# STATION.net
KiCad netlist of a schematic drawn in Altium Designer
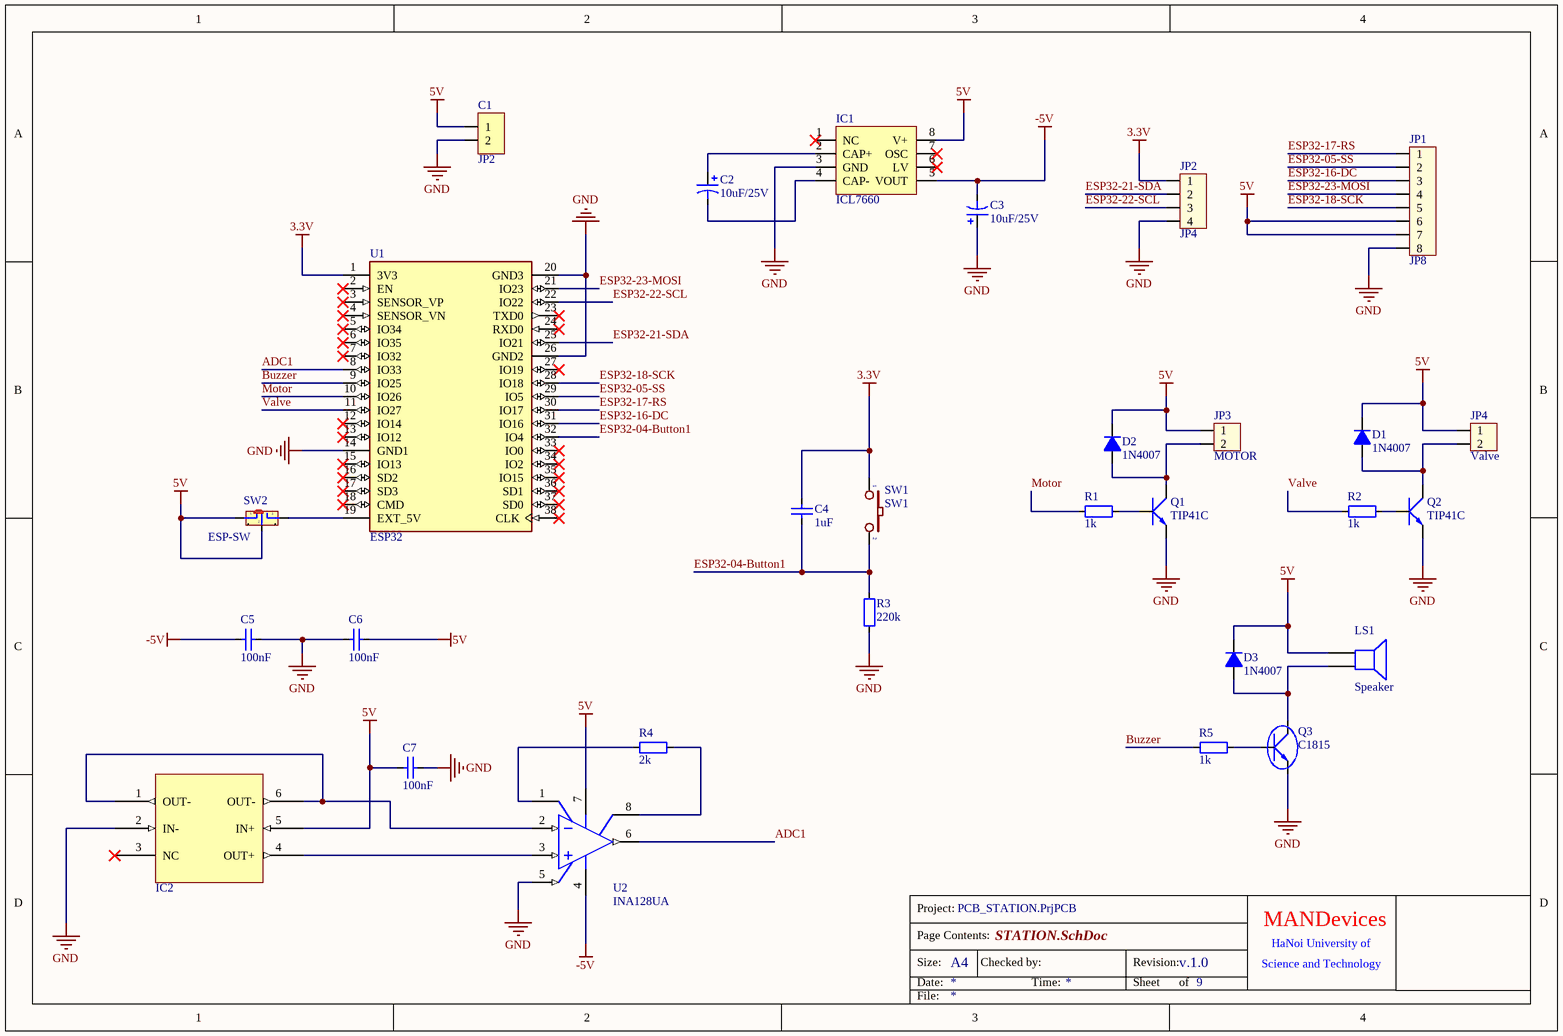
[diagram p0: STATION.SchDoc]

(export (version "E")
  (design (tool "Eeschema 10.0.6"))
  (components
    (comp (ref "C1")
      (value "JP2")
      (footprint "JP2-C1T")
      (description "WR-PHD 2.54 mm Angled Socket Header")
      (fields
        (field (name "MANUFACTURER") "Würth Elektronik eiSos GmbH")
        (field (name "PARTNO") "613002143121")
        (field (name "CREATED BY") "Karrer Zheng")
      )
      (libsource (lib "My Library") (part "JP2"))
    )
    (comp (ref "C2")
      (value "10uF/25V")
      (footprint "C8mm")
      (description "Polarized Capacitor (Axial)")
      (fields (field (name "PUBLISHER") "Altium Limited"))
      (libsource (lib "My Library") (part "Cap Pol"))
    )
    (comp (ref "C3")
      (value "10uF/25V")
      (footprint "C8mm")
      (description "Polarized Capacitor (Axial)")
      (fields (field (name "PUBLISHER") "Altium Limited"))
      (libsource (lib "My Library") (part "Cap Pol"))
    )
    (comp (ref "C4")
      (value "1uF")
      (footprint "CAP_0805")
      (description "Capacitor")
      (fields (field (name "PUBLISHER") "Altium Limited"))
      (libsource (lib "My Library") (part "CapSMD"))
    )
    (comp (ref "C5")
      (value "100nF")
      (footprint "CAP_0805")
      (description "Capacitor")
      (fields (field (name "PUBLISHER") "Altium Limited"))
      (libsource (lib "My Library") (part "CapSMD"))
    )
    (comp (ref "C6")
      (value "100nF")
      (footprint "CAP_0805")
      (description "Capacitor")
      (fields (field (name "PUBLISHER") "Altium Limited"))
      (libsource (lib "My Library") (part "CapSMD"))
    )
    (comp (ref "C7")
      (value "100nF")
      (footprint "CAP_0805")
      (description "Capacitor")
      (fields (field (name "PUBLISHER") "Altium Limited"))
      (libsource (lib "My Library") (part "CapSMD"))
    )
    (comp (ref "D1")
      (value "1N4007")
      (footprint "SMA")
      (description "Diode 1A")
      (libsource (lib "My Library") (part "D1A"))
    )
    (comp (ref "D2")
      (value "1N4007")
      (footprint "SMA")
      (description "Diode 1A")
      (libsource (lib "My Library") (part "D1A"))
    )
    (comp (ref "D3")
      (value "1N4007")
      (footprint "SMA")
      (description "Diode 1A")
      (libsource (lib "My Library") (part "D1A"))
    )
    (comp (ref "IC1")
      (value "ICL7660")
      (footprint "SOP-8")
      (description "CMOS Voltage Converters")
      (fields (field (name "CREATOR") "Nguyen Ba Bien"))
      (libsource (lib "My Library") (part "ICL7660"))
    )
    (comp (ref "IC2")
      (value "MPS20N0040D-D")
      (footprint "SOP-6")
      (description "Pressure Sensor")
      (libsource (lib "My Library") (part "MPS20N0040D-D"))
    )
    (comp (ref "JP1")
      (value "JP8")
      (footprint "CON8")
      (description "Connector 8")
      (libsource (lib "My Library") (part "Con8"))
    )
    (comp (ref "JP2")
      (value "JP4")
      (footprint "CON4")
      (description "Connector 4")
      (libsource (lib "My Library") (part "Con4"))
    )
    (comp (ref "JP3")
      (value "MOTOR")
      (footprint "CON2")
      (description "Connector 2")
      (libsource (lib "My Library") (part "Con2"))
    )
    (comp (ref "JP4")
      (value "Valve")
      (footprint "CON2")
      (description "Connector 2")
      (libsource (lib "My Library") (part "Con2"))
    )
    (comp (ref "LS1")
      (value "Speaker")
      (footprint "SPEAKER")
      (description "Loudspeaker")
      (fields (field (name "PUBLISHER") "Altium Limited"))
      (libsource (lib "My Library") (part "Speaker"))
    )
    (comp (ref "Q1")
      (value "TIP41C")
      (footprint "TO-252")
      (description "NPN 2W, BCE")
      (libsource (lib "My Library") (part "TIP41C"))
    )
    (comp (ref "Q2")
      (value "TIP41C")
      (footprint "TO-252")
      (description "NPN 2W, BCE")
      (libsource (lib "My Library") (part "TIP41C"))
    )
    (comp (ref "Q3")
      (value "C1815")
      (footprint "SOT23")
      (description "Transistor")
      (libsource (lib "My Library") (part "2SC5200"))
    )
    (comp (ref "R1")
      (value "1k")
      (footprint "RES-SMD-0805")
      (description "Resistor")
      (fields
        (field (name "MANUFACTURER") "Generic Components")
        (field (name "PUBLISHER") "Altium Hobart Technology Centre")
      )
      (libsource (lib "My Library") (part "Resistor - SMD"))
    )
    (comp (ref "R2")
      (value "1k")
      (footprint "RES-SMD-0805")
      (description "Resistor")
      (fields
        (field (name "MANUFACTURER") "Generic Components")
        (field (name "PUBLISHER") "Altium Hobart Technology Centre")
      )
      (libsource (lib "My Library") (part "Resistor - SMD"))
    )
    (comp (ref "R3")
      (value "220k")
      (footprint "RES-SMD-0805")
      (description "Resistor")
      (fields
        (field (name "MANUFACTURER") "Generic Components")
        (field (name "PUBLISHER") "Altium Hobart Technology Centre")
      )
      (libsource (lib "My Library") (part "Resistor - SMD"))
    )
    (comp (ref "R4")
      (value "2k")
      (footprint "RES-SMD-0805")
      (description "Resistor")
      (fields
        (field (name "MANUFACTURER") "Generic Components")
        (field (name "PUBLISHER") "Altium Hobart Technology Centre")
      )
      (libsource (lib "My Library") (part "Resistor - SMD"))
    )
    (comp (ref "R5")
      (value "1k")
      (footprint "RES-SMD-0805")
      (description "Resistor")
      (fields
        (field (name "MANUFACTURER") "Generic Components")
        (field (name "PUBLISHER") "Altium Hobart Technology Centre")
      )
      (libsource (lib "My Library") (part "Resistor - SMD"))
    )
    (comp (ref "SW1")
      (value "SW1")
      (footprint "SW2")
      (description "Switch button 2 pin")
      (libsource (lib "My Library") (part "SW2"))
    )
    (comp (ref "SW2")
      (value "ESP-SW")
      (footprint "SW102")
      (description "Switch 102 on Broad")
      (libsource (lib "My Library") (part "SW102A"))
    )
    (comp (ref "U1")
      (value "ESP32")
      (footprint "MODULE_ESP32-DEVKITC-32D")
      (description "EVAL BOARD FOR ESP-WROOM-32")
      (fields (field (name "MP") "ESP32-DEVKITC-32D") (field (name "MF") "Espressif Systems"))
      (libsource (lib "Rover_lite_Lib") (part "ESP32-DEVKITC-32D"))
    )
    (comp (ref "U2")
      (value "INA128UA")
      (footprint "SOP-8")
      (description "Low-Cost, Low-Power Instrumentation Amplifier")
      (fields (field (name "PUBLISHER") "Altium Limited"))
      (libsource (lib "My Library") (part "AD620AN"))
    )
  )
  (nets
    (net (code "1") (name "-5V") (class "Default")
      (node (ref "C3") (pin "2") (pinfunction "2_2") (pintype "passive"))
      (node (ref "C5") (pin "1") (pinfunction "1_1") (pintype "passive"))
      (node (ref "IC1") (pin "5") (pinfunction "VOUT_5") (pintype "passive"))
      (node (ref "U2") (pin "4") (pinfunction "V-_4") (pintype "power_in"))
    )
    (net (code "2") (name "/ADC1") (class "Default")
      (node (ref "U1") (pin "8") (pinfunction "IO33_8") (pintype "bidirectional"))
      (node (ref "U2") (pin "6") (pinfunction "OUT_6") (pintype "output"))
    )
    (net (code "3") (name "/Buzzer") (class "Default")
      (node (ref "R5") (pin "2") (pinfunction "2_2") (pintype "passive"))
      (node (ref "U1") (pin "9") (pinfunction "IO25_9") (pintype "bidirectional"))
    )
    (net (code "4") (name "/ESP32-04-Button1") (class "Default")
      (node (ref "C4") (pin "1") (pinfunction "1_1") (pintype "passive"))
      (node (ref "R3") (pin "2") (pinfunction "2_2") (pintype "passive"))
      (node (ref "SW1") (pin "2") (pinfunction "2_2") (pintype "passive"))
      (node (ref "U1") (pin "32") (pinfunction "IO4_32") (pintype "bidirectional"))
    )
    (net (code "5") (name "/ESP32-05-SS") (class "Default")
      (node (ref "JP1") (pin "2") (pinfunction "2_2") (pintype "passive"))
      (node (ref "U1") (pin "29") (pinfunction "IO5_29") (pintype "bidirectional"))
    )
    (net (code "6") (name "/ESP32-16-DC") (class "Default")
      (node (ref "JP1") (pin "3") (pinfunction "3_3") (pintype "passive"))
      (node (ref "U1") (pin "31") (pinfunction "IO16_31") (pintype "bidirectional"))
    )
    (net (code "7") (name "/ESP32-17-RS") (class "Default")
      (node (ref "JP1") (pin "1") (pinfunction "1_1") (pintype "passive"))
      (node (ref "U1") (pin "30") (pinfunction "IO17_30") (pintype "bidirectional"))
    )
    (net (code "8") (name "/ESP32-18-SCK") (class "Default")
      (node (ref "JP1") (pin "5") (pinfunction "5_5") (pintype "passive"))
      (node (ref "U1") (pin "28") (pinfunction "IO18_28") (pintype "bidirectional"))
    )
    (net (code "9") (name "/ESP32-21-SDA") (class "Default")
      (node (ref "JP2") (pin "2") (pinfunction "2_2") (pintype "passive"))
      (node (ref "U1") (pin "25") (pinfunction "IO21_25") (pintype "bidirectional"))
    )
    (net (code "10") (name "/ESP32-22-SCL") (class "Default")
      (node (ref "JP2") (pin "3") (pinfunction "3_3") (pintype "passive"))
      (node (ref "U1") (pin "22") (pinfunction "IO22_22") (pintype "bidirectional"))
    )
    (net (code "11") (name "/ESP32-23-MOSI") (class "Default")
      (node (ref "JP1") (pin "4") (pinfunction "4_4") (pintype "passive"))
      (node (ref "U1") (pin "21") (pinfunction "IO23_21") (pintype "bidirectional"))
    )
    (net (code "12") (name "/Motor") (class "Default")
      (node (ref "R1") (pin "2") (pinfunction "2_2") (pintype "passive"))
      (node (ref "U1") (pin "10") (pinfunction "IO26_10") (pintype "bidirectional"))
    )
    (net (code "13") (name "/Valve") (class "Default")
      (node (ref "R2") (pin "2") (pinfunction "2_2") (pintype "passive"))
      (node (ref "U1") (pin "11") (pinfunction "IO27_11") (pintype "bidirectional"))
    )
    (net (code "14") (name "3.3V") (class "Default")
      (node (ref "C4") (pin "2") (pinfunction "2_2") (pintype "passive"))
      (node (ref "JP2") (pin "1") (pinfunction "1_1") (pintype "passive"))
      (node (ref "SW1") (pin "1") (pinfunction "1_1") (pintype "passive"))
      (node (ref "U1") (pin "1") (pinfunction "3V3_1") (pintype "power_in"))
    )
    (net (code "15") (name "5V") (class "Default")
      (node (ref "C1") (pin "1") (pinfunction "1_1") (pintype "passive"))
      (node (ref "C6") (pin "2") (pinfunction "2_2") (pintype "passive"))
      (node (ref "C7") (pin "1") (pinfunction "1_1") (pintype "passive"))
      (node (ref "D1") (pin "2") (pinfunction "K_2") (pintype "passive"))
      (node (ref "D2") (pin "2") (pinfunction "K_2") (pintype "passive"))
      (node (ref "D3") (pin "2") (pinfunction "K_2") (pintype "passive"))
      (node (ref "IC1") (pin "8") (pinfunction "V+_8") (pintype "passive"))
      (node (ref "IC2") (pin "5") (pinfunction "IN+_5") (pintype "input"))
      (node (ref "JP1") (pin "6") (pinfunction "6_6") (pintype "passive"))
      (node (ref "JP1") (pin "7") (pinfunction "7_7") (pintype "passive"))
      (node (ref "JP3") (pin "1") (pinfunction "1_1") (pintype "passive"))
      (node (ref "JP4") (pin "1") (pinfunction "1_1") (pintype "passive"))
      (node (ref "LS1") (pin "1") (pinfunction "1_1") (pintype "passive"))
      (node (ref "SW2") (pin "1") (pinfunction "1_1") (pintype "passive"))
      (node (ref "SW2") (pin "2") (pinfunction "2_2") (pintype "passive"))
      (node (ref "U2") (pin "7") (pinfunction "V+_7") (pintype "power_in"))
    )
    (net (code "16") (name "GND") (class "Default")
      (node (ref "C1") (pin "2") (pinfunction "2_2") (pintype "passive"))
      (node (ref "C3") (pin "1") (pinfunction "1_1") (pintype "passive"))
      (node (ref "C5") (pin "2") (pinfunction "2_2") (pintype "passive"))
      (node (ref "C6") (pin "1") (pinfunction "1_1") (pintype "passive"))
      (node (ref "C7") (pin "2") (pinfunction "2_2") (pintype "passive"))
      (node (ref "IC1") (pin "3") (pinfunction "GND_3") (pintype "passive"))
      (node (ref "IC2") (pin "2") (pinfunction "IN-_2") (pintype "input"))
      (node (ref "JP1") (pin "8") (pinfunction "8_8") (pintype "passive"))
      (node (ref "JP2") (pin "4") (pinfunction "4_4") (pintype "passive"))
      (node (ref "Q1") (pin "3") (pinfunction "E_3") (pintype "passive"))
      (node (ref "Q2") (pin "3") (pinfunction "E_3") (pintype "passive"))
      (node (ref "Q3") (pin "3") (pinfunction "E_3") (pintype "passive"))
      (node (ref "R3") (pin "1") (pinfunction "1_1") (pintype "passive"))
      (node (ref "U1") (pin "14") (pinfunction "GND1_14") (pintype "power_in"))
      (node (ref "U1") (pin "20") (pinfunction "GND3_20") (pintype "power_in"))
      (node (ref "U1") (pin "26") (pinfunction "GND2_26") (pintype "power_in"))
      (node (ref "U2") (pin "5") (pinfunction "REF_5") (pintype "input"))
    )
    (net (code "17") (name "Net-(D1-A)") (class "Default")
      (node (ref "D1") (pin "1") (pinfunction "A_1") (pintype "passive"))
      (node (ref "JP4") (pin "2") (pinfunction "2_2") (pintype "passive"))
      (node (ref "Q2") (pin "2") (pinfunction "C_2") (pintype "passive"))
    )
    (net (code "18") (name "Net-(D2-A)") (class "Default")
      (node (ref "D2") (pin "1") (pinfunction "A_1") (pintype "passive"))
      (node (ref "JP3") (pin "2") (pinfunction "2_2") (pintype "passive"))
      (node (ref "Q1") (pin "2") (pinfunction "C_2") (pintype "passive"))
    )
    (net (code "19") (name "Net-(D3-A)") (class "Default")
      (node (ref "D3") (pin "1") (pinfunction "A_1") (pintype "passive"))
      (node (ref "LS1") (pin "2") (pinfunction "2_2") (pintype "passive"))
      (node (ref "Q3") (pin "2") (pinfunction "C_2") (pintype "passive"))
    )
    (net (code "20") (name "Net-(IC1-CAP+)") (class "Default")
      (node (ref "C2") (pin "1") (pinfunction "1_1") (pintype "passive"))
      (node (ref "IC1") (pin "2") (pinfunction "CAP+_2") (pintype "passive"))
    )
    (net (code "21") (name "Net-(IC1-CAP-)") (class "Default")
      (node (ref "C2") (pin "2") (pinfunction "2_2") (pintype "passive"))
      (node (ref "IC1") (pin "4") (pinfunction "CAP-_4") (pintype "passive"))
    )
    (net (code "22") (name "Net-(IC2-OUT+)") (class "Default")
      (node (ref "IC2") (pin "4") (pinfunction "OUT+_4") (pintype "output"))
      (node (ref "U2") (pin "3") (pinfunction "+IN_3") (pintype "input"))
    )
    (net (code "23") (name "Net-(Q1-B)") (class "Default")
      (node (ref "Q1") (pin "1") (pinfunction "B_1") (pintype "passive"))
      (node (ref "R1") (pin "1") (pinfunction "1_1") (pintype "passive"))
    )
    (net (code "24") (name "Net-(Q2-B)") (class "Default")
      (node (ref "Q2") (pin "1") (pinfunction "B_1") (pintype "passive"))
      (node (ref "R2") (pin "1") (pinfunction "1_1") (pintype "passive"))
    )
    (net (code "25") (name "Net-(Q3-B)") (class "Default")
      (node (ref "Q3") (pin "1") (pinfunction "B_1") (pintype "passive"))
      (node (ref "R5") (pin "1") (pinfunction "1_1") (pintype "passive"))
    )
    (net (code "26") (name "Net-(R4-Pad1)") (class "Default")
      (node (ref "R4") (pin "1") (pinfunction "1_1") (pintype "passive"))
      (node (ref "U2") (pin "8") (pinfunction "RG_8") (pintype "passive"))
    )
    (net (code "27") (name "Net-(R4-Pad2)") (class "Default")
      (node (ref "R4") (pin "2") (pinfunction "2_2") (pintype "passive"))
      (node (ref "U2") (pin "1") (pinfunction "RG_1") (pintype "passive"))
    )
    (net (code "28") (name "Net-(U1-EXT_5V)") (class "Default")
      (node (ref "SW2") (pin "3") (pinfunction "3_3") (pintype "passive"))
      (node (ref "U1") (pin "19") (pinfunction "EXT_5V_19") (pintype "power_in"))
    )
    (net (code "29") (name "Net-(U2--IN)") (class "Default")
      (node (ref "IC2") (pin "1") (pinfunction "OUT-_1") (pintype "output"))
      (node (ref "IC2") (pin "6") (pinfunction "OUT-_6") (pintype "output"))
      (node (ref "U2") (pin "2") (pinfunction "-IN_2") (pintype "input"))
    )
    (net (code "30") (name "unconnected-(IC1-LV-Pad6)") (class "Default")
      (node (ref "IC1") (pin "6") (pinfunction "LV_6") (pintype "passive+no_connect"))
    )
    (net (code "31") (name "unconnected-(IC1-NC-Pad1)") (class "Default")
      (node (ref "IC1") (pin "1") (pinfunction "NC_1") (pintype "passive+no_connect"))
    )
    (net (code "32") (name "unconnected-(IC1-OSC-Pad7)") (class "Default")
      (node (ref "IC1") (pin "7") (pinfunction "OSC_7") (pintype "passive+no_connect"))
    )
    (net (code "33") (name "unconnected-(IC2-NC-Pad3)") (class "Default")
      (node (ref "IC2") (pin "3") (pinfunction "NC_3") (pintype "passive+no_connect"))
    )
    (net (code "34") (name "unconnected-(SW2-Pad4)") (class "Default")
      (node (ref "SW2") (pin "4") (pinfunction "4_4") (pintype "passive"))
    )
    (net (code "35") (name "unconnected-(SW2-Pad5)") (class "Default")
      (node (ref "SW2") (pin "5") (pinfunction "5_5") (pintype "passive"))
    )
    (net (code "36") (name "unconnected-(U1-CLK-Pad38)") (class "Default")
      (node (ref "U1") (pin "38") (pinfunction "CLK_38") (pintype "input+no_connect"))
    )
    (net (code "37") (name "unconnected-(U1-CMD-Pad18)") (class "Default")
      (node (ref "U1") (pin "18") (pinfunction "CMD_18") (pintype "bidirectional+no_connect"))
    )
    (net (code "38") (name "unconnected-(U1-EN-Pad2)") (class "Default")
      (node (ref "U1") (pin "2") (pinfunction "EN_2") (pintype "input+no_connect"))
    )
    (net (code "39") (name "unconnected-(U1-IO0-Pad33)") (class "Default")
      (node (ref "U1") (pin "33") (pinfunction "IO0_33") (pintype "bidirectional+no_connect"))
    )
    (net (code "40") (name "unconnected-(U1-IO2-Pad34)") (class "Default")
      (node (ref "U1") (pin "34") (pinfunction "IO2_34") (pintype "bidirectional+no_connect"))
    )
    (net (code "41") (name "unconnected-(U1-IO12-Pad13)") (class "Default")
      (node (ref "U1") (pin "13") (pinfunction "IO12_13") (pintype "bidirectional+no_connect"))
    )
    (net (code "42") (name "unconnected-(U1-IO13-Pad15)") (class "Default")
      (node (ref "U1") (pin "15") (pinfunction "IO13_15") (pintype "bidirectional+no_connect"))
    )
    (net (code "43") (name "unconnected-(U1-IO14-Pad12)") (class "Default")
      (node (ref "U1") (pin "12") (pinfunction "IO14_12") (pintype "bidirectional+no_connect"))
    )
    (net (code "44") (name "unconnected-(U1-IO15-Pad35)") (class "Default")
      (node (ref "U1") (pin "35") (pinfunction "IO15_35") (pintype "bidirectional+no_connect"))
    )
    (net (code "45") (name "unconnected-(U1-IO19-Pad27)") (class "Default")
      (node (ref "U1") (pin "27") (pinfunction "IO19_27") (pintype "bidirectional+no_connect"))
    )
    (net (code "46") (name "unconnected-(U1-IO32-Pad7)") (class "Default")
      (node (ref "U1") (pin "7") (pinfunction "IO32_7") (pintype "bidirectional+no_connect"))
    )
    (net (code "47") (name "unconnected-(U1-IO34-Pad5)") (class "Default")
      (node (ref "U1") (pin "5") (pinfunction "IO34_5") (pintype "bidirectional+no_connect"))
    )
    (net (code "48") (name "unconnected-(U1-IO35-Pad6)") (class "Default")
      (node (ref "U1") (pin "6") (pinfunction "IO35_6") (pintype "bidirectional+no_connect"))
    )
    (net (code "49") (name "unconnected-(U1-RXD0-Pad24)") (class "Default")
      (node (ref "U1") (pin "24") (pinfunction "RXD0_24") (pintype "input+no_connect"))
    )
    (net (code "50") (name "unconnected-(U1-SD0-Pad37)") (class "Default")
      (node (ref "U1") (pin "37") (pinfunction "SD0_37") (pintype "bidirectional+no_connect"))
    )
    (net (code "51") (name "unconnected-(U1-SD1-Pad36)") (class "Default")
      (node (ref "U1") (pin "36") (pinfunction "SD1_36") (pintype "bidirectional+no_connect"))
    )
    (net (code "52") (name "unconnected-(U1-SD2-Pad16)") (class "Default")
      (node (ref "U1") (pin "16") (pinfunction "SD2_16") (pintype "bidirectional+no_connect"))
    )
    (net (code "53") (name "unconnected-(U1-SD3-Pad17)") (class "Default")
      (node (ref "U1") (pin "17") (pinfunction "SD3_17") (pintype "bidirectional+no_connect"))
    )
    (net (code "54") (name "unconnected-(U1-SENSOR_VN-Pad4)") (class "Default")
      (node (ref "U1") (pin "4") (pinfunction "SENSOR_VN_4") (pintype "input+no_connect"))
    )
    (net (code "55") (name "unconnected-(U1-SENSOR_VP-Pad3)") (class "Default")
      (node (ref "U1") (pin "3") (pinfunction "SENSOR_VP_3") (pintype "input+no_connect"))
    )
    (net (code "56") (name "unconnected-(U1-TXD0-Pad23)") (class "Default")
      (node (ref "U1") (pin "23") (pinfunction "TXD0_23") (pintype "output+no_connect"))
    )
  )
)
